# INA219x2_FeatherWing.net
KiCad netlist of a schematic drawn in EAGLE
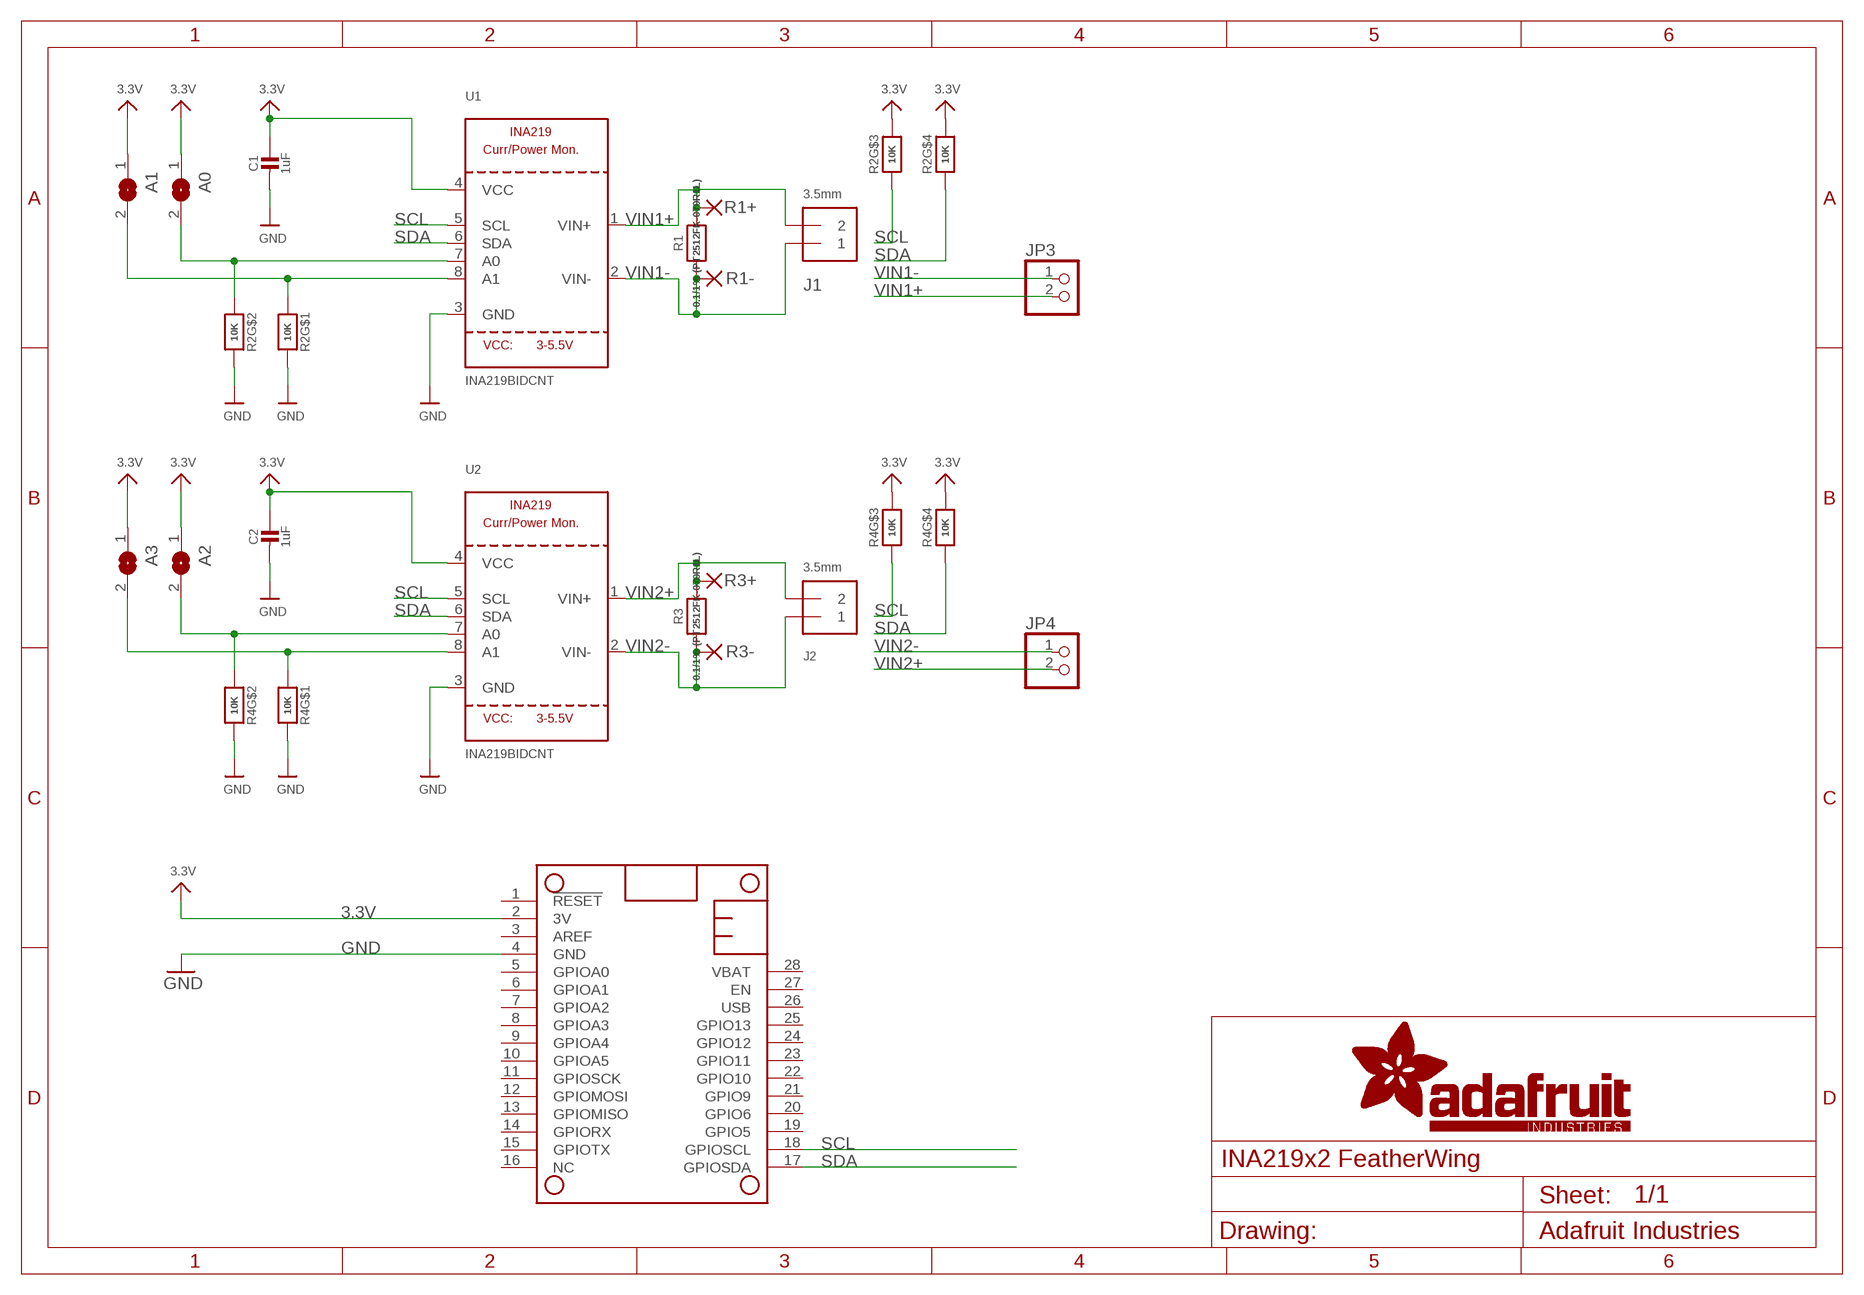
[diagram p0: schematic, sheet 1]

(export (version "E")
  (design (tool "Eeschema 10.0.6"))
  (components
    (comp (ref "A0")
      (value "SOLDERJUMPERREFLOW_NOPASTE")
      (footprint "eagle-import:SOLDERJUMPER_REFLOW_NOPASTE")
      (libsource (lib "eagle-import") (part "SOLDERJUMPERREFLOW_NOPASTE"))
    )
    (comp (ref "A1")
      (value "SOLDERJUMPERREFLOW_NOPASTE")
      (footprint "eagle-import:SOLDERJUMPER_REFLOW_NOPASTE")
      (libsource (lib "eagle-import") (part "SOLDERJUMPERREFLOW_NOPASTE"))
    )
    (comp (ref "A2")
      (value "SOLDERJUMPERREFLOW_NOPASTE")
      (footprint "eagle-import:SOLDERJUMPER_REFLOW_NOPASTE")
      (libsource (lib "eagle-import") (part "SOLDERJUMPERREFLOW_NOPASTE"))
    )
    (comp (ref "A3")
      (value "SOLDERJUMPERREFLOW_NOPASTE")
      (footprint "eagle-import:SOLDERJUMPER_REFLOW_NOPASTE")
      (libsource (lib "eagle-import") (part "SOLDERJUMPERREFLOW_NOPASTE"))
    )
    (comp (ref "C1")
      (value "1uF")
      (footprint "eagle-import:0805-NO@1")
      (libsource (lib "eagle-import") (part "CAP_CERAMIC0805-NOOUTLINE"))
    )
    (comp (ref "C2")
      (value "1uF")
      (footprint "eagle-import:0805-NO@1")
      (libsource (lib "eagle-import") (part "CAP_CERAMIC0805-NOOUTLINE"))
    )
    (comp (ref "J1")
      (value "3.5mm")
      (footprint "eagle-import:TERMBLOCK_1X2-3.5MM")
      (libsource (lib "eagle-import") (part "TERMBLOCK_1X2"))
    )
    (comp (ref "J2")
      (value "3.5mm")
      (footprint "eagle-import:TERMBLOCK_1X2-3.5MM")
      (libsource (lib "eagle-import") (part "TERMBLOCK_1X2"))
    )
    (comp (ref "JP3")
      (value "HEADER-1X2ROUND")
      (footprint "eagle-import:1X02_ROUND")
      (libsource (lib "eagle-import") (part "HEADER-1X2ROUND"))
    )
    (comp (ref "JP4")
      (value "HEADER-1X2ROUND")
      (footprint "eagle-import:1X02_ROUND")
      (libsource (lib "eagle-import") (part "HEADER-1X2ROUND"))
    )
    (comp (ref "MS1")
      (value "FEATHERWING")
      (footprint "eagle-import:FEATHERWING")
      (libsource (lib "eagle-import") (part "FEATHERWING"))
    )
    (comp (ref "R1")
      (value "0.1/1% (PT2512FK-070R1L)")
      (footprint "eagle-import:2512")
      (libsource (lib "eagle-import") (part "RESISTOR2512"))
    )
    (comp (ref "R1+")
      (value "1,6/0,9")
      (footprint "eagle-import:1,6_0,9")
      (libsource (lib "eagle-import") (part "1,6/0,9"))
    )
    (comp (ref "R1-")
      (value "1,6/0,9")
      (footprint "eagle-import:1,6_0,9")
      (libsource (lib "eagle-import") (part "1,6/0,9"))
    )
    (comp (ref "R2")
      (value "10K")
      (footprint "eagle-import:RESPACK_4X0603")
      (libsource (lib "eagle-import") (part "RESISTOR_4PACK"))
    )
    (comp (ref "R3")
      (value "0.1/1% (PT2512FK-070R1L)")
      (footprint "eagle-import:2512")
      (libsource (lib "eagle-import") (part "RESISTOR2512"))
    )
    (comp (ref "R3+")
      (value "1,6/0,9")
      (footprint "eagle-import:1,6_0,9")
      (libsource (lib "eagle-import") (part "1,6/0,9"))
    )
    (comp (ref "R3-")
      (value "1,6/0,9")
      (footprint "eagle-import:1,6_0,9")
      (libsource (lib "eagle-import") (part "1,6/0,9"))
    )
    (comp (ref "R4")
      (value "10K")
      (footprint "eagle-import:RESPACK_4X0603")
      (libsource (lib "eagle-import") (part "RESISTOR_4PACK"))
    )
    (comp (ref "U1")
      (value "INA219BIDCNT")
      (footprint "eagle-import:SOT23-8")
      (libsource (lib "eagle-import") (part "INA219"))
    )
    (comp (ref "U2")
      (value "INA219BIDCNT")
      (footprint "eagle-import:SOT23-8")
      (libsource (lib "eagle-import") (part "INA219"))
    )
  )
  (nets
    (net (code "1") (name "/SCL") (class "Default")
      (node (ref "MS1") (pin "18") (pinfunction "GPIOSCL_18") (pintype "bidirectional"))
      (node (ref "R2") (pin "3") (pinfunction "1_3") (pintype "passive"))
      (node (ref "R4") (pin "3") (pinfunction "1_3") (pintype "passive"))
      (node (ref "U1") (pin "5") (pinfunction "SCL_5") (pintype "bidirectional"))
      (node (ref "U2") (pin "5") (pinfunction "SCL_5") (pintype "bidirectional"))
    )
    (net (code "2") (name "/SDA") (class "Default")
      (node (ref "MS1") (pin "17") (pinfunction "GPIOSDA_17") (pintype "bidirectional"))
      (node (ref "R2") (pin "4") (pinfunction "1_4") (pintype "passive"))
      (node (ref "R4") (pin "4") (pinfunction "1_4") (pintype "passive"))
      (node (ref "U1") (pin "6") (pinfunction "SDA_6") (pintype "bidirectional"))
      (node (ref "U2") (pin "6") (pinfunction "SDA_6") (pintype "bidirectional"))
    )
    (net (code "3") (name "/USB") (class "Default")
      (node (ref "MS1") (pin "26") (pinfunction "USB_26") (pintype "power_in"))
    )
    (net (code "4") (name "/VBAT") (class "Default")
      (node (ref "MS1") (pin "28") (pinfunction "VBAT_28") (pintype "power_in"))
    )
    (net (code "5") (name "/VIN1+") (class "Default")
      (node (ref "J1") (pin "2") (pinfunction "2_2") (pintype "passive"))
      (node (ref "JP3") (pin "2") (pinfunction "2_2") (pintype "passive"))
      (node (ref "R1") (pin "2") (pinfunction "2_2") (pintype "passive"))
      (node (ref "R1+") (pin "1") (pinfunction "P_1") (pintype "passive"))
      (node (ref "U1") (pin "1") (pinfunction "VIN+_1") (pintype "bidirectional"))
    )
    (net (code "6") (name "/VIN1-") (class "Default")
      (node (ref "J1") (pin "1") (pinfunction "1_1") (pintype "passive"))
      (node (ref "JP3") (pin "1") (pinfunction "1_1") (pintype "passive"))
      (node (ref "R1") (pin "1") (pinfunction "1_1") (pintype "passive"))
      (node (ref "R1-") (pin "1") (pinfunction "P_1") (pintype "passive"))
      (node (ref "U1") (pin "2") (pinfunction "VIN-_2") (pintype "bidirectional"))
    )
    (net (code "7") (name "/VIN2+") (class "Default")
      (node (ref "J2") (pin "2") (pinfunction "2_2") (pintype "passive"))
      (node (ref "JP4") (pin "2") (pinfunction "2_2") (pintype "passive"))
      (node (ref "R3") (pin "2") (pinfunction "2_2") (pintype "passive"))
      (node (ref "R3+") (pin "1") (pinfunction "P_1") (pintype "passive"))
      (node (ref "U2") (pin "1") (pinfunction "VIN+_1") (pintype "bidirectional"))
    )
    (net (code "8") (name "/VIN2-") (class "Default")
      (node (ref "J2") (pin "1") (pinfunction "1_1") (pintype "passive"))
      (node (ref "JP4") (pin "1") (pinfunction "1_1") (pintype "passive"))
      (node (ref "R3") (pin "1") (pinfunction "1_1") (pintype "passive"))
      (node (ref "R3-") (pin "1") (pinfunction "P_1") (pintype "passive"))
      (node (ref "U2") (pin "2") (pinfunction "VIN-_2") (pintype "bidirectional"))
    )
    (net (code "9") (name "3.3V") (class "Default")
      (node (ref "A0") (pin "1") (pinfunction "1_1") (pintype "passive"))
      (node (ref "A1") (pin "1") (pinfunction "1_1") (pintype "passive"))
      (node (ref "A2") (pin "1") (pinfunction "1_1") (pintype "passive"))
      (node (ref "A3") (pin "1") (pinfunction "1_1") (pintype "passive"))
      (node (ref "C1") (pin "1") (pinfunction "1_1") (pintype "passive"))
      (node (ref "C2") (pin "1") (pinfunction "1_1") (pintype "passive"))
      (node (ref "MS1") (pin "2") (pinfunction "3V_2") (pintype "power_in"))
      (node (ref "R2") (pin "5") (pinfunction "2_5") (pintype "passive"))
      (node (ref "R2") (pin "6") (pinfunction "2_6") (pintype "passive"))
      (node (ref "R4") (pin "5") (pinfunction "2_5") (pintype "passive"))
      (node (ref "R4") (pin "6") (pinfunction "2_6") (pintype "passive"))
      (node (ref "U1") (pin "4") (pinfunction "VCC_4") (pintype "power_in"))
      (node (ref "U2") (pin "4") (pinfunction "VCC_4") (pintype "power_in"))
    )
    (net (code "10") (name "GND") (class "Default")
      (node (ref "C1") (pin "2") (pinfunction "2_2") (pintype "passive"))
      (node (ref "C2") (pin "2") (pinfunction "2_2") (pintype "passive"))
      (node (ref "MS1") (pin "4") (pinfunction "GND_4") (pintype "power_in"))
      (node (ref "R2") (pin "7") (pinfunction "2_7") (pintype "passive"))
      (node (ref "R2") (pin "8") (pinfunction "2_8") (pintype "passive"))
      (node (ref "R4") (pin "7") (pinfunction "2_7") (pintype "passive"))
      (node (ref "R4") (pin "8") (pinfunction "2_8") (pintype "passive"))
      (node (ref "U1") (pin "3") (pinfunction "GND_3") (pintype "power_in"))
      (node (ref "U2") (pin "3") (pinfunction "GND_3") (pintype "power_in"))
    )
    (net (code "11") (name "Net-(R2B-1)") (class "Default")
      (node (ref "A0") (pin "2") (pinfunction "2_2") (pintype "passive"))
      (node (ref "R2") (pin "2") (pinfunction "1_2") (pintype "passive"))
      (node (ref "U1") (pin "7") (pinfunction "A0_7") (pintype "bidirectional"))
    )
    (net (code "12") (name "Net-(R4B-1)") (class "Default")
      (node (ref "A2") (pin "2") (pinfunction "2_2") (pintype "passive"))
      (node (ref "R4") (pin "2") (pinfunction "1_2") (pintype "passive"))
      (node (ref "U2") (pin "7") (pinfunction "A0_7") (pintype "bidirectional"))
    )
    (net (code "13") (name "Net-(U1-A1)") (class "Default")
      (node (ref "A1") (pin "2") (pinfunction "2_2") (pintype "passive"))
      (node (ref "R2") (pin "1") (pinfunction "1_1") (pintype "passive"))
      (node (ref "U1") (pin "8") (pinfunction "A1_8") (pintype "bidirectional"))
    )
    (net (code "14") (name "Net-(U2-A1)") (class "Default")
      (node (ref "A3") (pin "2") (pinfunction "2_2") (pintype "passive"))
      (node (ref "R4") (pin "1") (pinfunction "1_1") (pintype "passive"))
      (node (ref "U2") (pin "8") (pinfunction "A1_8") (pintype "bidirectional"))
    )
    (net (code "15") (name "unconnected-(MS1-AREF-Pad3)") (class "Default")
      (node (ref "MS1") (pin "3") (pinfunction "AREF_3") (pintype "passive"))
    )
    (net (code "16") (name "unconnected-(MS1-EN-Pad27)") (class "Default")
      (node (ref "MS1") (pin "27") (pinfunction "EN_27") (pintype "passive"))
    )
    (net (code "17") (name "unconnected-(MS1-GPIO5-Pad19)") (class "Default")
      (node (ref "MS1") (pin "19") (pinfunction "GPIO5_19") (pintype "bidirectional"))
    )
    (net (code "18") (name "unconnected-(MS1-GPIO6-Pad20)") (class "Default")
      (node (ref "MS1") (pin "20") (pinfunction "GPIO6_20") (pintype "bidirectional"))
    )
    (net (code "19") (name "unconnected-(MS1-GPIO9-Pad21)") (class "Default")
      (node (ref "MS1") (pin "21") (pinfunction "GPIO9_21") (pintype "bidirectional"))
    )
    (net (code "20") (name "unconnected-(MS1-GPIO10-Pad22)") (class "Default")
      (node (ref "MS1") (pin "22") (pinfunction "GPIO10_22") (pintype "bidirectional"))
    )
    (net (code "21") (name "unconnected-(MS1-GPIO11-Pad23)") (class "Default")
      (node (ref "MS1") (pin "23") (pinfunction "GPIO11_23") (pintype "bidirectional"))
    )
    (net (code "22") (name "unconnected-(MS1-GPIO12-Pad24)") (class "Default")
      (node (ref "MS1") (pin "24") (pinfunction "GPIO12_24") (pintype "bidirectional"))
    )
    (net (code "23") (name "unconnected-(MS1-GPIO13-Pad25)") (class "Default")
      (node (ref "MS1") (pin "25") (pinfunction "GPIO13_25") (pintype "bidirectional"))
    )
    (net (code "24") (name "unconnected-(MS1-GPIOA0-Pad5)") (class "Default")
      (node (ref "MS1") (pin "5") (pinfunction "GPIOA0_5") (pintype "bidirectional"))
    )
    (net (code "25") (name "unconnected-(MS1-GPIOA1-Pad6)") (class "Default")
      (node (ref "MS1") (pin "6") (pinfunction "GPIOA1_6") (pintype "bidirectional"))
    )
    (net (code "26") (name "unconnected-(MS1-GPIOA2-Pad7)") (class "Default")
      (node (ref "MS1") (pin "7") (pinfunction "GPIOA2_7") (pintype "bidirectional"))
    )
    (net (code "27") (name "unconnected-(MS1-GPIOA3-Pad8)") (class "Default")
      (node (ref "MS1") (pin "8") (pinfunction "GPIOA3_8") (pintype "bidirectional"))
    )
    (net (code "28") (name "unconnected-(MS1-GPIOA4-Pad9)") (class "Default")
      (node (ref "MS1") (pin "9") (pinfunction "GPIOA4_9") (pintype "bidirectional"))
    )
    (net (code "29") (name "unconnected-(MS1-GPIOA5-Pad10)") (class "Default")
      (node (ref "MS1") (pin "10") (pinfunction "GPIOA5_10") (pintype "bidirectional"))
    )
    (net (code "30") (name "unconnected-(MS1-GPIOMISO-Pad13)") (class "Default")
      (node (ref "MS1") (pin "13") (pinfunction "GPIOMISO_13") (pintype "bidirectional"))
    )
    (net (code "31") (name "unconnected-(MS1-GPIOMOSI-Pad12)") (class "Default")
      (node (ref "MS1") (pin "12") (pinfunction "GPIOMOSI_12") (pintype "bidirectional"))
    )
    (net (code "32") (name "unconnected-(MS1-GPIORX-Pad14)") (class "Default")
      (node (ref "MS1") (pin "14") (pinfunction "GPIORX_14") (pintype "bidirectional"))
    )
    (net (code "33") (name "unconnected-(MS1-GPIOSCK-Pad11)") (class "Default")
      (node (ref "MS1") (pin "11") (pinfunction "GPIOSCK_11") (pintype "bidirectional"))
    )
    (net (code "34") (name "unconnected-(MS1-GPIOTX-Pad15)") (class "Default")
      (node (ref "MS1") (pin "15") (pinfunction "GPIOTX_15") (pintype "bidirectional"))
    )
    (net (code "35") (name "unconnected-(MS1-NC-Pad16)") (class "Default")
      (node (ref "MS1") (pin "16") (pinfunction "NC_16") (pintype "passive"))
    )
    (net (code "36") (name "unconnected-(MS1-~{RESET}-Pad1)") (class "Default")
      (node (ref "MS1") (pin "1") (pinfunction "~{RESET}_1") (pintype "input"))
    )
  )
)
